# RN41.net
KiCad netlist of a schematic drawn in EAGLE
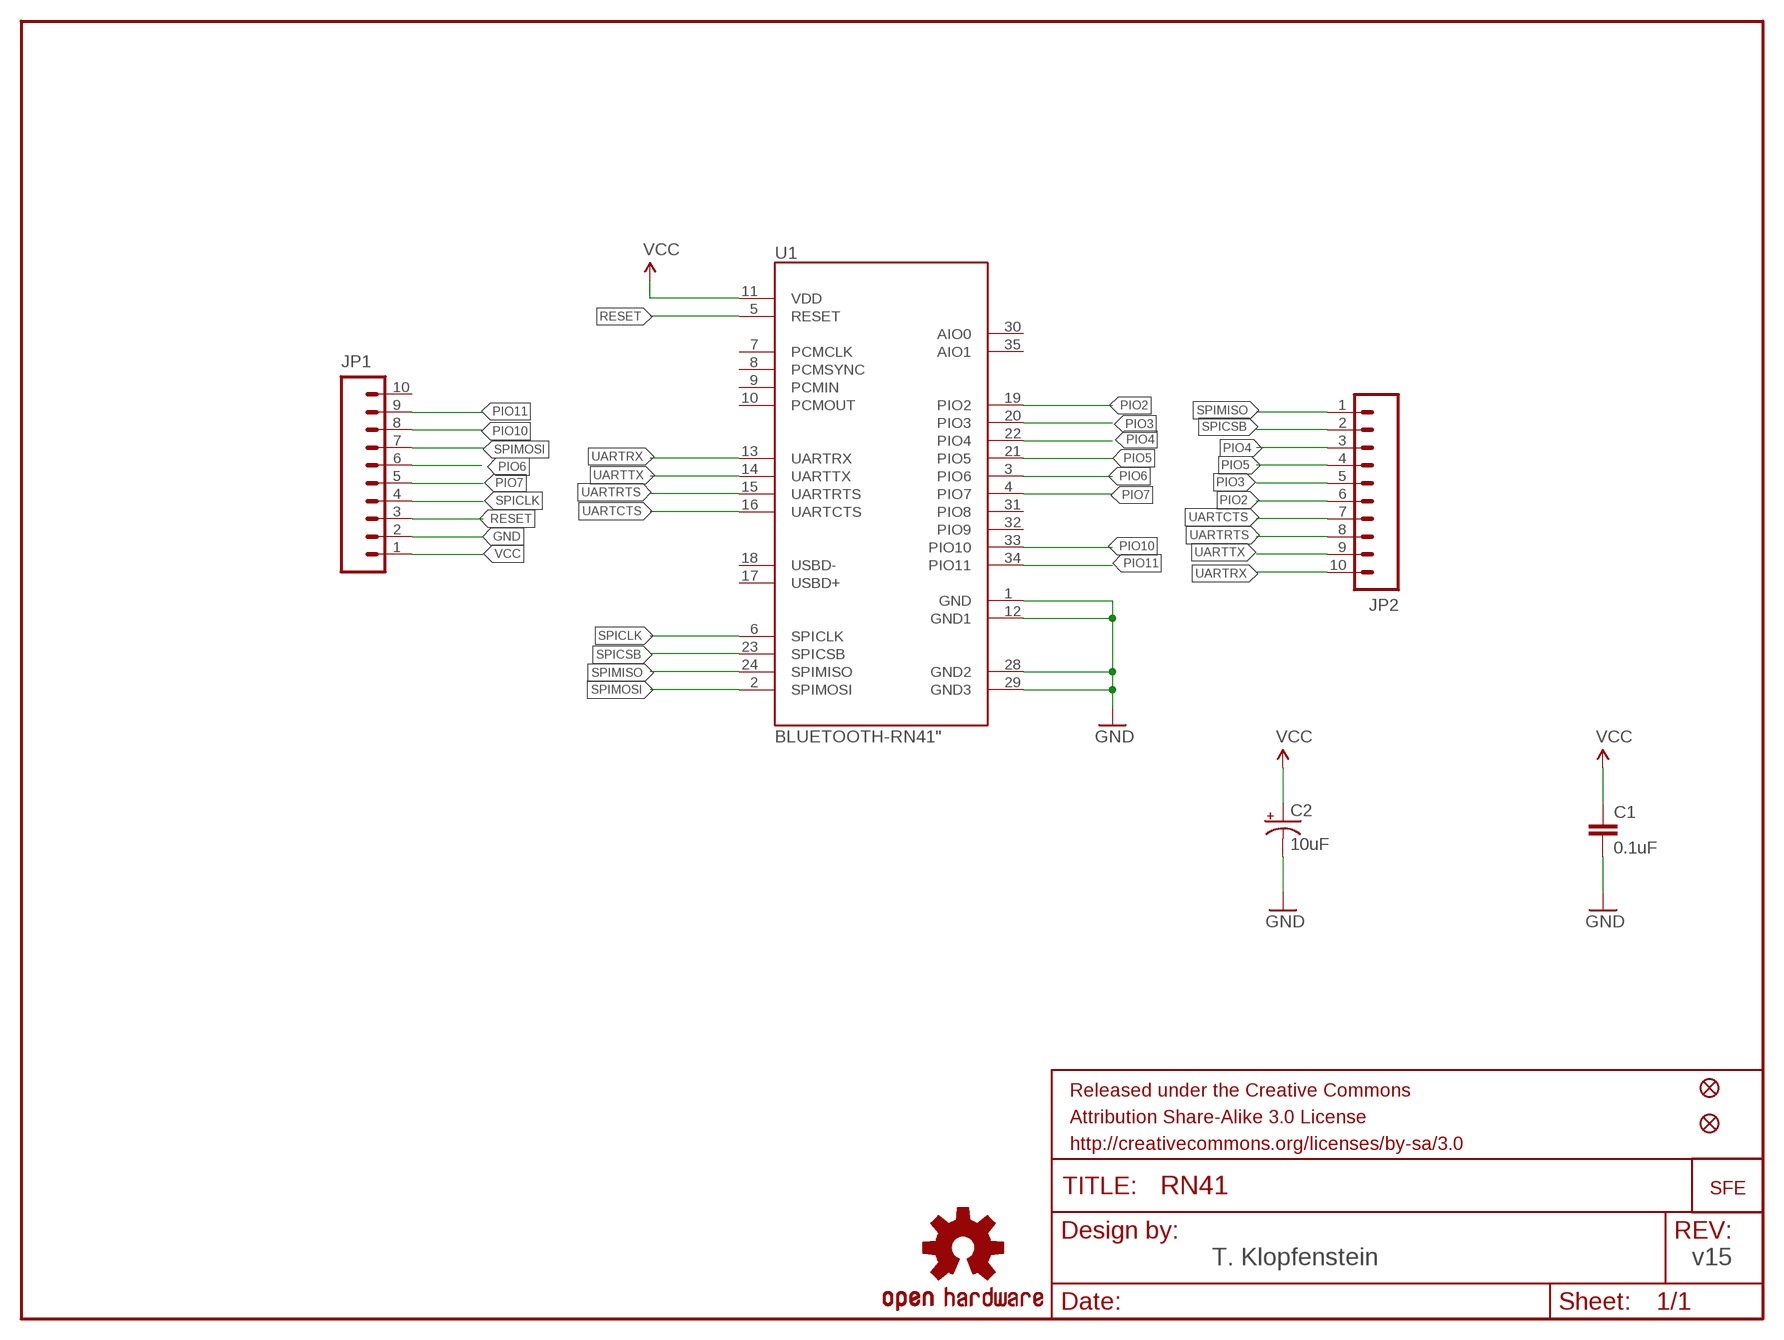
[diagram p0: schematic, sheet 1]

(export (version "E")
  (design (tool "Eeschema 10.0.6"))
  (components
    (comp (ref "C1")
      (value "0.1uF")
      (footprint "eagle-import:0603-CAP")
      (libsource (lib "eagle-import") (part "CAP0603-CAP"))
    )
    (comp (ref "C2")
      (value "10uF")
      (footprint "eagle-import:EIA3216")
      (libsource (lib "eagle-import") (part "CAP_POL1206"))
    )
    (comp (ref "FID1")
      (value "FIDUCIALUFIDUCIAL")
      (footprint "eagle-import:MICRO-FIDUCIAL")
      (libsource (lib "eagle-import") (part "FIDUCIALUFIDUCIAL"))
    )
    (comp (ref "FID2")
      (value "FIDUCIALUFIDUCIAL")
      (footprint "eagle-import:MICRO-FIDUCIAL")
      (libsource (lib "eagle-import") (part "FIDUCIALUFIDUCIAL"))
    )
    (comp (ref "FRAME1")
      (value "FRAME-LETTER")
      (footprint "eagle-import:CREATIVE_COMMONS")
      (libsource (lib "eagle-import") (part "FRAME-LETTER"))
    )
    (comp (ref "JP1")
      (value "M10\"")
      (footprint "eagle-import:1X10")
      (libsource (lib "eagle-import") (part "M10{dblquote}"))
    )
    (comp (ref "JP2")
      (value "M10\"")
      (footprint "eagle-import:1X10")
      (libsource (lib "eagle-import") (part "M10{dblquote}"))
    )
    (comp (ref "LOGO1")
      (value "OSHW-LOGOS")
      (footprint "eagle-import:OSHW-LOGO-S")
      (libsource (lib "eagle-import") (part "OSHW-LOGOS"))
    )
    (comp (ref "U$1")
      (value "LOGO-SFENEW")
      (footprint "eagle-import:SFE-NEW-WEBLOGO")
      (libsource (lib "eagle-import") (part "LOGO-SFENEW"))
    )
    (comp (ref "U1")
      (value "BLUETOOTH-RN41\"")
      (footprint "eagle-import:RN41")
      (libsource (lib "eagle-import") (part "BLUETOOTH-RN41{dblquote}"))
    )
  )
  (nets
    (net (code "1") (name "GND") (class "Default")
      (node (ref "C1") (pin "2") (pinfunction "2_2") (pintype "passive"))
      (node (ref "C2") (pin "C") (pinfunction "-_C") (pintype "passive"))
      (node (ref "JP1") (pin "2") (pinfunction "2_2") (pintype "passive"))
      (node (ref "U1") (pin "1") (pinfunction "GND_1") (pintype "bidirectional"))
      (node (ref "U1") (pin "12") (pinfunction "GND1_12") (pintype "bidirectional"))
      (node (ref "U1") (pin "28") (pinfunction "GND2_28") (pintype "bidirectional"))
      (node (ref "U1") (pin "29") (pinfunction "GND3_29") (pintype "bidirectional"))
    )
    (net (code "2") (name "PIO2") (class "Default")
      (node (ref "JP2") (pin "6") (pinfunction "6_6") (pintype "passive"))
      (node (ref "U1") (pin "19") (pinfunction "PIO2_19") (pintype "bidirectional"))
    )
    (net (code "3") (name "PIO3") (class "Default")
      (node (ref "JP2") (pin "5") (pinfunction "5_5") (pintype "passive"))
      (node (ref "U1") (pin "20") (pinfunction "PIO3_20") (pintype "bidirectional"))
    )
    (net (code "4") (name "PIO4") (class "Default")
      (node (ref "JP2") (pin "3") (pinfunction "3_3") (pintype "passive"))
      (node (ref "U1") (pin "22") (pinfunction "PIO4_22") (pintype "bidirectional"))
    )
    (net (code "5") (name "PIO5") (class "Default")
      (node (ref "JP2") (pin "4") (pinfunction "4_4") (pintype "passive"))
      (node (ref "U1") (pin "21") (pinfunction "PIO5_21") (pintype "bidirectional"))
    )
    (net (code "6") (name "PIO6") (class "Default")
      (node (ref "JP1") (pin "6") (pinfunction "6_6") (pintype "passive"))
      (node (ref "U1") (pin "3") (pinfunction "PIO6_3") (pintype "bidirectional"))
    )
    (net (code "7") (name "PIO7") (class "Default")
      (node (ref "JP1") (pin "5") (pinfunction "5_5") (pintype "passive"))
      (node (ref "U1") (pin "4") (pinfunction "PIO7_4") (pintype "bidirectional"))
    )
    (net (code "8") (name "PIO10") (class "Default")
      (node (ref "JP1") (pin "8") (pinfunction "8_8") (pintype "passive"))
      (node (ref "U1") (pin "33") (pinfunction "PIO10_33") (pintype "bidirectional"))
    )
    (net (code "9") (name "PIO11") (class "Default")
      (node (ref "JP1") (pin "9") (pinfunction "9_9") (pintype "passive"))
      (node (ref "U1") (pin "34") (pinfunction "PIO11_34") (pintype "bidirectional"))
    )
    (net (code "10") (name "RESET") (class "Default")
      (node (ref "JP1") (pin "3") (pinfunction "3_3") (pintype "passive"))
      (node (ref "U1") (pin "5") (pinfunction "RESET_5") (pintype "bidirectional"))
    )
    (net (code "11") (name "SPICLK") (class "Default")
      (node (ref "JP1") (pin "4") (pinfunction "4_4") (pintype "passive"))
      (node (ref "U1") (pin "6") (pinfunction "SPICLK_6") (pintype "bidirectional"))
    )
    (net (code "12") (name "SPICSB") (class "Default")
      (node (ref "JP2") (pin "2") (pinfunction "2_2") (pintype "passive"))
      (node (ref "U1") (pin "23") (pinfunction "SPICSB_23") (pintype "bidirectional"))
    )
    (net (code "13") (name "SPIMISO") (class "Default")
      (node (ref "JP2") (pin "1") (pinfunction "1_1") (pintype "passive"))
      (node (ref "U1") (pin "24") (pinfunction "SPIMISO_24") (pintype "bidirectional"))
    )
    (net (code "14") (name "SPIMOSI") (class "Default")
      (node (ref "JP1") (pin "7") (pinfunction "7_7") (pintype "passive"))
      (node (ref "U1") (pin "2") (pinfunction "SPIMOSI_2") (pintype "bidirectional"))
    )
    (net (code "15") (name "UARTCTS") (class "Default")
      (node (ref "JP2") (pin "7") (pinfunction "7_7") (pintype "passive"))
      (node (ref "U1") (pin "16") (pinfunction "UARTCTS_16") (pintype "bidirectional"))
    )
    (net (code "16") (name "UARTRTS") (class "Default")
      (node (ref "JP2") (pin "8") (pinfunction "8_8") (pintype "passive"))
      (node (ref "U1") (pin "15") (pinfunction "UARTRTS_15") (pintype "bidirectional"))
    )
    (net (code "17") (name "UARTRX") (class "Default")
      (node (ref "JP2") (pin "10") (pinfunction "10_10") (pintype "passive"))
      (node (ref "U1") (pin "13") (pinfunction "UARTRX_13") (pintype "bidirectional"))
    )
    (net (code "18") (name "UARTTX") (class "Default")
      (node (ref "JP2") (pin "9") (pinfunction "9_9") (pintype "passive"))
      (node (ref "U1") (pin "14") (pinfunction "UARTTX_14") (pintype "bidirectional"))
    )
    (net (code "19") (name "VCC") (class "Default")
      (node (ref "C1") (pin "1") (pinfunction "1_1") (pintype "passive"))
      (node (ref "C2") (pin "A") (pinfunction "+_A") (pintype "passive"))
      (node (ref "JP1") (pin "1") (pinfunction "1_1") (pintype "passive"))
      (node (ref "U1") (pin "11") (pinfunction "VDD_11") (pintype "bidirectional"))
    )
    (net (code "20") (name "unconnected-(JP1-Pad10)") (class "Default")
      (node (ref "JP1") (pin "10") (pinfunction "10_10") (pintype "passive"))
    )
    (net (code "21") (name "unconnected-(U1-AIO0-Pad30)") (class "Default")
      (node (ref "U1") (pin "30") (pinfunction "AIO0_30") (pintype "bidirectional"))
    )
    (net (code "22") (name "unconnected-(U1-AIO1-Pad35)") (class "Default")
      (node (ref "U1") (pin "35") (pinfunction "AIO1_35") (pintype "bidirectional"))
    )
    (net (code "23") (name "unconnected-(U1-PCMCLK-Pad7)") (class "Default")
      (node (ref "U1") (pin "7") (pinfunction "PCMCLK_7") (pintype "bidirectional"))
    )
    (net (code "24") (name "unconnected-(U1-PCMIN-Pad9)") (class "Default")
      (node (ref "U1") (pin "9") (pinfunction "PCMIN_9") (pintype "bidirectional"))
    )
    (net (code "25") (name "unconnected-(U1-PCMOUT-Pad10)") (class "Default")
      (node (ref "U1") (pin "10") (pinfunction "PCMOUT_10") (pintype "bidirectional"))
    )
    (net (code "26") (name "unconnected-(U1-PCMSYNC-Pad8)") (class "Default")
      (node (ref "U1") (pin "8") (pinfunction "PCMSYNC_8") (pintype "bidirectional"))
    )
    (net (code "27") (name "unconnected-(U1-PIO8-Pad31)") (class "Default")
      (node (ref "U1") (pin "31") (pinfunction "PIO8_31") (pintype "bidirectional"))
    )
    (net (code "28") (name "unconnected-(U1-PIO9-Pad32)") (class "Default")
      (node (ref "U1") (pin "32") (pinfunction "PIO9_32") (pintype "bidirectional"))
    )
    (net (code "29") (name "unconnected-(U1-USBD+-Pad17)") (class "Default")
      (node (ref "U1") (pin "17") (pinfunction "USBD+_17") (pintype "bidirectional"))
    )
    (net (code "30") (name "unconnected-(U1-USBD--Pad18)") (class "Default")
      (node (ref "U1") (pin "18") (pinfunction "USBD-_18") (pintype "bidirectional"))
    )
  )
)
